# Card_Edge_Connector.net
KiCad netlist of a schematic drawn in Altium Designer
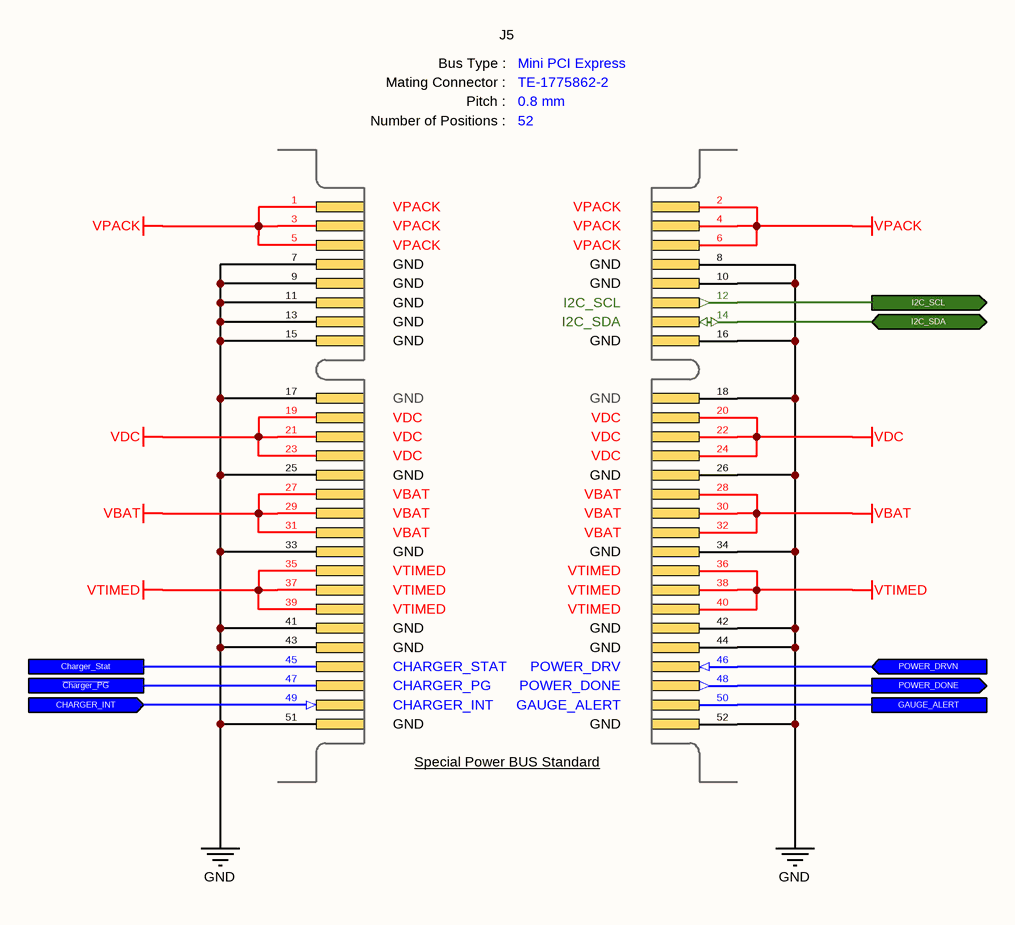
[diagram p0: Card Edge Connector.SchDoc]

(export (version "E")
  (design (tool "Eeschema 10.0.6"))
  (components
    (comp (ref "J5")
      (value "Connector - Mini PCI-E [Power]")
      (footprint "PCB - Mini PCI Express")
      (description "Mini PCI-Express gold finger connector.")
      (fields
        (field (name "BUS TYPE") "Mini PCI Express")
        (field (name "MATING CONNECTOR") "TE-1775862-2")
        (field (name "PITCH") "0.8 mm")
        (field (name "NUMBER OF POSITIONS") "52")
      )
      (libsource (lib "P101DA_Library") (part "Connector - Mini PCI-E [Power]"))
    )
  )
  (nets
    (net (code "1") (name "/CHARGER_INT") (class "Default")
      (node (ref "J5") (pin "49") (pinfunction "Pin-49_49") (pintype "input"))
    )
    (net (code "2") (name "/Charger_Stat") (class "Default")
      (node (ref "J5") (pin "45") (pinfunction "Pin-45_45") (pintype "passive"))
    )
    (net (code "3") (name "/GAUGE_ALERT") (class "Default")
      (node (ref "J5") (pin "50") (pinfunction "Pin-50_50") (pintype "passive"))
    )
    (net (code "4") (name "/I2C_SCL") (class "Default")
      (node (ref "J5") (pin "12") (pinfunction "Pin-12_12") (pintype "output"))
    )
    (net (code "5") (name "/I2C_SDA") (class "Default")
      (node (ref "J5") (pin "14") (pinfunction "Pin-14_14") (pintype "bidirectional"))
    )
    (net (code "6") (name "/POWER_DONE") (class "Default")
      (node (ref "J5") (pin "48") (pinfunction "Pin-48_48") (pintype "output"))
    )
    (net (code "7") (name "/POWER_DRVN") (class "Default")
      (node (ref "J5") (pin "46") (pinfunction "Pin-46_46") (pintype "input"))
    )
    (net (code "8") (name "/~{Charger_PG}") (class "Default")
      (node (ref "J5") (pin "47") (pinfunction "Pin-47_47") (pintype "passive"))
    )
    (net (code "9") (name "GND") (class "Default")
      (node (ref "J5") (pin "10") (pinfunction "Pin-10_10") (pintype "power_in"))
      (node (ref "J5") (pin "11") (pinfunction "Pin-11_11") (pintype "power_in"))
      (node (ref "J5") (pin "13") (pinfunction "Pin-13_13") (pintype "power_in"))
      (node (ref "J5") (pin "15") (pinfunction "Pin-15_15") (pintype "power_in"))
      (node (ref "J5") (pin "16") (pinfunction "Pin-16_16") (pintype "power_in"))
      (node (ref "J5") (pin "17") (pinfunction "Pin-17_17") (pintype "power_in"))
      (node (ref "J5") (pin "18") (pinfunction "Pin-18_18") (pintype "power_in"))
      (node (ref "J5") (pin "25") (pinfunction "Pin-25_25") (pintype "passive"))
      (node (ref "J5") (pin "26") (pinfunction "Pin-26_26") (pintype "passive"))
      (node (ref "J5") (pin "33") (pinfunction "Pin-33_33") (pintype "power_in"))
      (node (ref "J5") (pin "34") (pinfunction "Pin-34_34") (pintype "power_in"))
      (node (ref "J5") (pin "41") (pinfunction "Pin-41_41") (pintype "power_in"))
      (node (ref "J5") (pin "42") (pinfunction "Pin-42_42") (pintype "power_in"))
      (node (ref "J5") (pin "43") (pinfunction "Pin-43_43") (pintype "passive"))
      (node (ref "J5") (pin "44") (pinfunction "Pin-44_44") (pintype "passive"))
      (node (ref "J5") (pin "51") (pinfunction "Pin-51_51") (pintype "power_in"))
      (node (ref "J5") (pin "52") (pinfunction "Pin-52_52") (pintype "power_in"))
      (node (ref "J5") (pin "7") (pinfunction "Pin-7_7") (pintype "power_in"))
      (node (ref "J5") (pin "8") (pinfunction "Pin-8_8") (pintype "power_in"))
      (node (ref "J5") (pin "9") (pinfunction "Pin-9_9") (pintype "power_in"))
    )
    (net (code "10") (name "VBAT") (class "Default")
      (node (ref "J5") (pin "27") (pinfunction "Pin-27_27") (pintype "power_in"))
      (node (ref "J5") (pin "28") (pinfunction "Pin-28_28") (pintype "power_in"))
      (node (ref "J5") (pin "29") (pinfunction "Pin-29_29") (pintype "power_in"))
      (node (ref "J5") (pin "30") (pinfunction "Pin-30_30") (pintype "power_in"))
      (node (ref "J5") (pin "31") (pinfunction "Pin-31_31") (pintype "power_in"))
      (node (ref "J5") (pin "32") (pinfunction "Pin-32_32") (pintype "power_in"))
    )
    (net (code "11") (name "VDC") (class "Default")
      (node (ref "J5") (pin "19") (pinfunction "Pin-19_19") (pintype "power_in"))
      (node (ref "J5") (pin "20") (pinfunction "Pin-20_20") (pintype "power_in"))
      (node (ref "J5") (pin "21") (pinfunction "Pin-21_21") (pintype "power_in"))
      (node (ref "J5") (pin "22") (pinfunction "Pin-22_22") (pintype "power_in"))
      (node (ref "J5") (pin "23") (pinfunction "Pin-23_23") (pintype "power_in"))
      (node (ref "J5") (pin "24") (pinfunction "Pin-24_24") (pintype "power_in"))
    )
    (net (code "12") (name "VPACK") (class "Default")
      (node (ref "J5") (pin "1") (pinfunction "Pin-1_1") (pintype "power_in"))
      (node (ref "J5") (pin "2") (pinfunction "Pin-2_2") (pintype "power_in"))
      (node (ref "J5") (pin "3") (pinfunction "Pin-3_3") (pintype "power_in"))
      (node (ref "J5") (pin "4") (pinfunction "Pin-4_4") (pintype "power_in"))
      (node (ref "J5") (pin "5") (pinfunction "Pin-5_5") (pintype "power_in"))
      (node (ref "J5") (pin "6") (pinfunction "Pin-6_6") (pintype "power_in"))
    )
    (net (code "13") (name "VTIMED") (class "Default")
      (node (ref "J5") (pin "35") (pinfunction "Pin-35_35") (pintype "power_in"))
      (node (ref "J5") (pin "36") (pinfunction "Pin-36_36") (pintype "power_in"))
      (node (ref "J5") (pin "37") (pinfunction "Pin-37_37") (pintype "power_in"))
      (node (ref "J5") (pin "38") (pinfunction "Pin-38_38") (pintype "power_in"))
      (node (ref "J5") (pin "39") (pinfunction "Pin-39_39") (pintype "power_in"))
      (node (ref "J5") (pin "40") (pinfunction "Pin-40_40") (pintype "power_in"))
    )
  )
)
